# arduino-to-headers-shield.net
KiCad netlist of a schematic drawn in Altium Designer
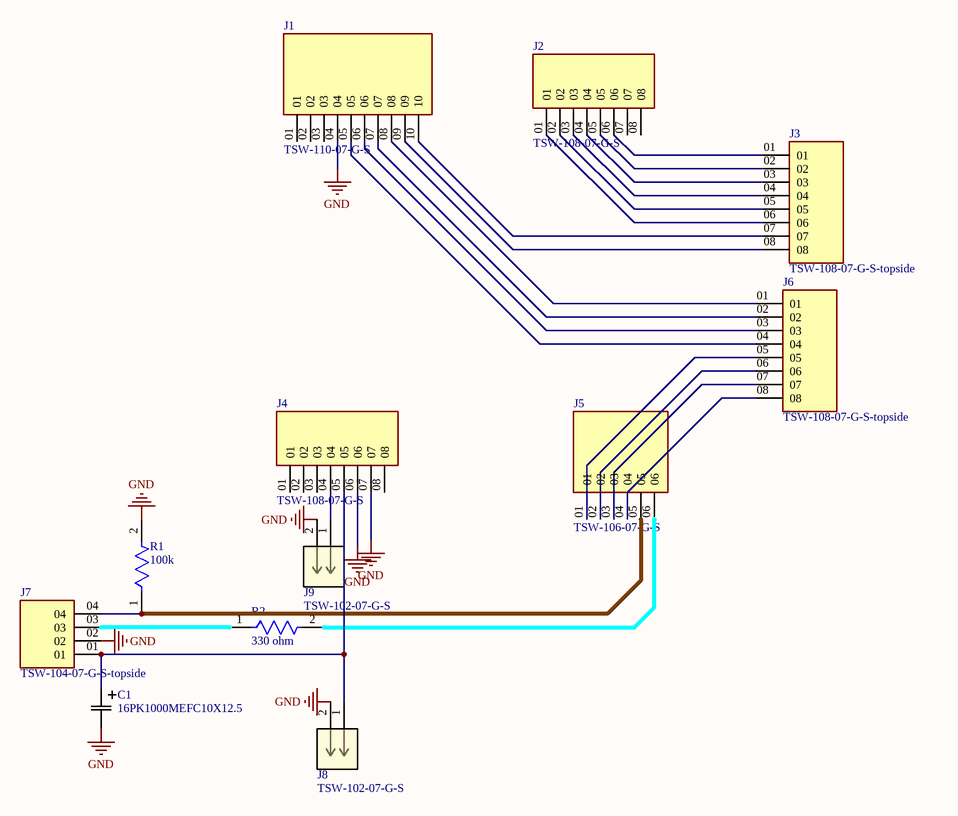
[diagram p0: arduino-to-headers-shield.SchDoc]

(export (version "E")
  (design (tool "Eeschema 10.0.6"))
  (components
    (comp (ref "C1")
      (value "16PK1000MEFC10X12.5")
      (footprint "CAP_PKPZ_10X12P5_LOW_RUB")
      (description "No Description Available")
      (fields (field (name "COPYRIGHT") "Copyright (C) 2024 Ultra Librarian. All rights reserved."))
      (libsource (lib "SchlibLafe") (part "16PK1000MEFC10X12.5"))
    )
    (comp (ref "J1")
      (value "TSW-110-07-G-S")
      (footprint "SAMTEC_TSW-110-07-G-S")
      (fields (field (name "MF") "Samtec Inc."))
      (libsource (lib "SchlibLafe") (part "TSW-110-07-G-S"))
    )
    (comp (ref "J2")
      (value "TSW-108-07-G-S")
      (footprint "SAMTEC_TSW-108-07-G-S")
      (description "TSW - Samtec 2.54mm Pin Header 10.92mm Overall Pin Length (07) - Fast Stock")
      (fields (field (name "MF") "Samtec Inc."))
      (libsource (lib "SchlibLafe") (part "TSW-108-07-G-S"))
    )
    (comp (ref "J3")
      (value "TSW-108-07-G-S-topside")
      (footprint "SAMTEC_TSW-108-07-G-S-topside")
      (description "TSW - Samtec 2.54mm Pin Header 10.92mm Overall Pin Length (07) - Fast Stock")
      (fields (field (name "MF") "Samtec Inc.") (field (name "MP") "TSW-108-07-G-S"))
      (libsource (lib "SchlibLafe") (part "TSW-108-07-G-S-topside"))
    )
    (comp (ref "J4")
      (value "TSW-108-07-G-S")
      (footprint "SAMTEC_TSW-108-07-G-S")
      (description "TSW - Samtec 2.54mm Pin Header 10.92mm Overall Pin Length (07) - Fast Stock")
      (fields (field (name "MF") "Samtec Inc."))
      (libsource (lib "SchlibLafe") (part "TSW-108-07-G-S"))
    )
    (comp (ref "J5")
      (value "TSW-106-07-G-S")
      (footprint "SAMTEC_TSW-106-07-G-S")
      (fields (field (name "MF") "Samtec Inc."))
      (libsource (lib "SchlibLafe") (part "TSW-106-07-G-S"))
    )
    (comp (ref "J6")
      (value "TSW-108-07-G-S-topside")
      (footprint "SAMTEC_TSW-108-07-G-S-topside")
      (description "TSW - Samtec 2.54mm Pin Header 10.92mm Overall Pin Length (07) - Fast Stock")
      (fields (field (name "MF") "Samtec Inc.") (field (name "MP") "TSW-108-07-G-S"))
      (libsource (lib "SchlibLafe") (part "TSW-108-07-G-S-topside"))
    )
    (comp (ref "J7")
      (value "TSW-104-07-G-S-topside")
      (footprint "SAMTEC_TSW-104-07-G-S-topside")
      (fields (field (name "MP") "altium_native_batch"))
      (libsource (lib "SchlibLafe") (part "TSW-104-07-G-S-topside"))
    )
    (comp (ref "J8")
      (value "TSW-102-07-G-S")
      (footprint "TSW-102-07-G-S-topside")
      (description "No Description Available")
      (fields (field (name "COPYRIGHT") "Copyright (C) 2024 Ultra Librarian. All rights reserved."))
      (libsource (lib "SchlibLafe") (part "TSW-102-07-G-S-topside"))
    )
    (comp (ref "J9")
      (value "TSW-102-07-G-S")
      (footprint "TSW-102-07-G-S-topside")
      (description "No Description Available")
      (fields (field (name "COPYRIGHT") "Copyright (C) 2024 Ultra Librarian. All rights reserved."))
      (libsource (lib "SchlibLafe") (part "TSW-102-07-G-S-topside"))
    )
    (comp (ref "R1")
      (value "100k")
      (footprint "FP-RLR07-MFG")
      (fields (field (name "TOLERANCE") "1%"))
      (libsource (lib "Altium Content Vault") (part "1029c3af85768c4190bb7ad29bc67b5"))
    )
    (comp (ref "R2")
      (value "330 ohm")
      (footprint "FP-RLR07-MFG")
      (fields (field (name "TOLERANCE") "1%"))
      (libsource (lib "Altium Content Vault") (part "1029c3af85768c4190bb7ad29bc67b5"))
    )
  )
  (nets
    (net (code "1") (name "GND") (class "Default")
      (node (ref "C1") (pin "2") (pinfunction "2_2") (pintype "passive"))
      (node (ref "J1") (pin "04") (pinfunction "04_04") (pintype "passive"))
      (node (ref "J4") (pin "06") (pinfunction "06_06") (pintype "passive"))
      (node (ref "J4") (pin "07") (pinfunction "07_07") (pintype "passive"))
      (node (ref "J7") (pin "02") (pinfunction "02_02") (pintype "passive"))
      (node (ref "J8") (pin "2") (pinfunction "2_2") (pintype "passive"))
      (node (ref "J9") (pin "2") (pinfunction "2_2") (pintype "passive"))
      (node (ref "R1") (pin "2") (pinfunction "2_2") (pintype "passive"))
    )
    (net (code "2") (name "Net-(C1-Pad1)") (class "Default")
      (node (ref "C1") (pin "1") (pinfunction "1_1") (pintype "passive"))
      (node (ref "J4") (pin "05") (pinfunction "05_05") (pintype "passive"))
      (node (ref "J7") (pin "01") (pinfunction "01_01") (pintype "passive"))
      (node (ref "J8") (pin "1") (pinfunction "1_1") (pintype "passive"))
    )
    (net (code "3") (name "Net-(J1-Pad05)") (class "Default")
      (node (ref "J1") (pin "05") (pinfunction "05_05") (pintype "passive"))
      (node (ref "J6") (pin "04") (pinfunction "04_04") (pintype "passive"))
    )
    (net (code "4") (name "Net-(J1-Pad06)") (class "Default")
      (node (ref "J1") (pin "06") (pinfunction "06_06") (pintype "passive"))
      (node (ref "J6") (pin "03") (pinfunction "03_03") (pintype "passive"))
    )
    (net (code "5") (name "Net-(J1-Pad07)") (class "Default")
      (node (ref "J1") (pin "07") (pinfunction "07_07") (pintype "passive"))
      (node (ref "J6") (pin "02") (pinfunction "02_02") (pintype "passive"))
    )
    (net (code "6") (name "Net-(J1-Pad08)") (class "Default")
      (node (ref "J1") (pin "08") (pinfunction "08_08") (pintype "passive"))
      (node (ref "J6") (pin "01") (pinfunction "01_01") (pintype "passive"))
    )
    (net (code "7") (name "Net-(J1-Pad09)") (class "Default")
      (node (ref "J1") (pin "09") (pinfunction "09_09") (pintype "passive"))
      (node (ref "J3") (pin "08") (pinfunction "08_08") (pintype "passive"))
    )
    (net (code "8") (name "Net-(J1-Pad10)") (class "Default")
      (node (ref "J1") (pin "10") (pinfunction "10_10") (pintype "passive"))
      (node (ref "J3") (pin "07") (pinfunction "07_07") (pintype "passive"))
    )
    (net (code "9") (name "Net-(J2-Pad01)") (class "Default")
      (node (ref "J2") (pin "01") (pinfunction "01_01") (pintype "passive"))
      (node (ref "J3") (pin "06") (pinfunction "06_06") (pintype "passive"))
    )
    (net (code "10") (name "Net-(J2-Pad02)") (class "Default")
      (node (ref "J2") (pin "02") (pinfunction "02_02") (pintype "passive"))
      (node (ref "J3") (pin "05") (pinfunction "05_05") (pintype "passive"))
    )
    (net (code "11") (name "Net-(J2-Pad03)") (class "Default")
      (node (ref "J2") (pin "03") (pinfunction "03_03") (pintype "passive"))
      (node (ref "J3") (pin "04") (pinfunction "04_04") (pintype "passive"))
    )
    (net (code "12") (name "Net-(J2-Pad04)") (class "Default")
      (node (ref "J2") (pin "04") (pinfunction "04_04") (pintype "passive"))
      (node (ref "J3") (pin "03") (pinfunction "03_03") (pintype "passive"))
    )
    (net (code "13") (name "Net-(J2-Pad05)") (class "Default")
      (node (ref "J2") (pin "05") (pinfunction "05_05") (pintype "passive"))
      (node (ref "J3") (pin "02") (pinfunction "02_02") (pintype "passive"))
    )
    (net (code "14") (name "Net-(J2-Pad06)") (class "Default")
      (node (ref "J2") (pin "06") (pinfunction "06_06") (pintype "passive"))
      (node (ref "J3") (pin "01") (pinfunction "01_01") (pintype "passive"))
    )
    (net (code "15") (name "Net-(J4-Pad04)") (class "Default")
      (node (ref "J4") (pin "04") (pinfunction "04_04") (pintype "passive"))
      (node (ref "J9") (pin "1") (pinfunction "1_1") (pintype "passive"))
    )
    (net (code "16") (name "Net-(J5-Pad01)") (class "Default")
      (node (ref "J5") (pin "01") (pinfunction "01_01") (pintype "passive"))
      (node (ref "J6") (pin "05") (pinfunction "05_05") (pintype "passive"))
    )
    (net (code "17") (name "Net-(J5-Pad02)") (class "Default")
      (node (ref "J5") (pin "02") (pinfunction "02_02") (pintype "passive"))
      (node (ref "J6") (pin "06") (pinfunction "06_06") (pintype "passive"))
    )
    (net (code "18") (name "Net-(J5-Pad03)") (class "Default")
      (node (ref "J5") (pin "03") (pinfunction "03_03") (pintype "passive"))
      (node (ref "J6") (pin "07") (pinfunction "07_07") (pintype "passive"))
    )
    (net (code "19") (name "Net-(J5-Pad04)") (class "Default")
      (node (ref "J5") (pin "04") (pinfunction "04_04") (pintype "passive"))
      (node (ref "J6") (pin "08") (pinfunction "08_08") (pintype "passive"))
    )
    (net (code "20") (name "Net-(J5-Pad05)") (class "Default")
      (node (ref "J5") (pin "05") (pinfunction "05_05") (pintype "passive"))
      (node (ref "J7") (pin "04") (pinfunction "04_04") (pintype "passive"))
      (node (ref "R1") (pin "1") (pinfunction "1_1") (pintype "passive"))
    )
    (net (code "21") (name "Net-(J5-Pad06)") (class "Default")
      (node (ref "J5") (pin "06") (pinfunction "06_06") (pintype "passive"))
      (node (ref "R2") (pin "2") (pinfunction "2_2") (pintype "passive"))
    )
    (net (code "22") (name "Net-(J7-Pad03)") (class "Default")
      (node (ref "J7") (pin "03") (pinfunction "03_03") (pintype "passive"))
      (node (ref "R2") (pin "1") (pinfunction "1_1") (pintype "passive"))
    )
    (net (code "23") (name "unconnected-(J1-Pad01)") (class "Default")
      (node (ref "J1") (pin "01") (pinfunction "01_01") (pintype "passive"))
    )
    (net (code "24") (name "unconnected-(J1-Pad02)") (class "Default")
      (node (ref "J1") (pin "02") (pinfunction "02_02") (pintype "passive"))
    )
    (net (code "25") (name "unconnected-(J1-Pad03)") (class "Default")
      (node (ref "J1") (pin "03") (pinfunction "03_03") (pintype "passive"))
    )
    (net (code "26") (name "unconnected-(J2-Pad07)") (class "Default")
      (node (ref "J2") (pin "07") (pinfunction "07_07") (pintype "passive"))
    )
    (net (code "27") (name "unconnected-(J2-Pad08)") (class "Default")
      (node (ref "J2") (pin "08") (pinfunction "08_08") (pintype "passive"))
    )
    (net (code "28") (name "unconnected-(J4-Pad01)") (class "Default")
      (node (ref "J4") (pin "01") (pinfunction "01_01") (pintype "passive"))
    )
    (net (code "29") (name "unconnected-(J4-Pad02)") (class "Default")
      (node (ref "J4") (pin "02") (pinfunction "02_02") (pintype "passive"))
    )
    (net (code "30") (name "unconnected-(J4-Pad03)") (class "Default")
      (node (ref "J4") (pin "03") (pinfunction "03_03") (pintype "passive"))
    )
    (net (code "31") (name "unconnected-(J4-Pad08)") (class "Default")
      (node (ref "J4") (pin "08") (pinfunction "08_08") (pintype "passive"))
    )
  )
)
